# LTC2485Shield.net
KiCad netlist of a schematic drawn in EAGLE
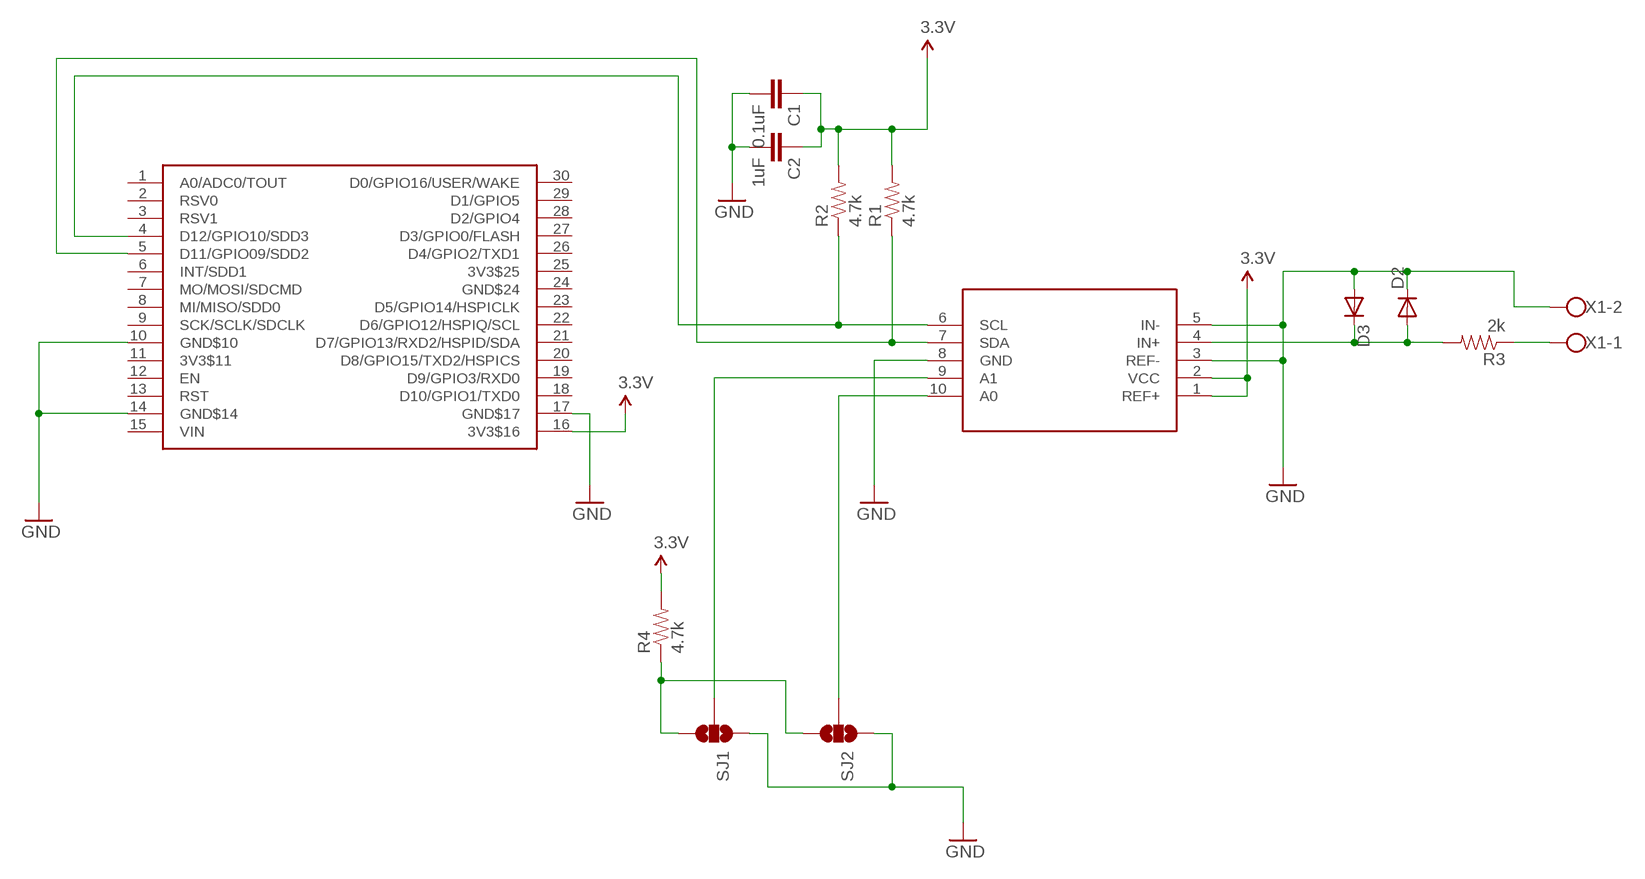
[diagram p0: schematic, sheet 1]

(export (version "E")
  (design (tool "Eeschema 10.0.6"))
  (components
    (comp (ref "C1")
      (value "0.1uF")
      (footprint "eagle-import:0402-CAP")
      (libsource (lib "eagle-import") (part "CAP0402-CAP"))
    )
    (comp (ref "C2")
      (value "1uF")
      (footprint "eagle-import:0402-CAP")
      (libsource (lib "eagle-import") (part "CAP0402-CAP"))
    )
    (comp (ref "D2")
      (value "DIODESOD")
      (footprint "eagle-import:SOD-323")
      (libsource (lib "eagle-import") (part "DIODESOD"))
    )
    (comp (ref "D3")
      (value "DIODESOD")
      (footprint "eagle-import:SOD-323")
      (libsource (lib "eagle-import") (part "DIODESOD"))
    )
    (comp (ref "R1")
      (value "4.7k")
      (footprint "eagle-import:0402-RES")
      (libsource (lib "eagle-import") (part "RESISTOR0402-RES"))
    )
    (comp (ref "R2")
      (value "4.7k")
      (footprint "eagle-import:0402-RES")
      (libsource (lib "eagle-import") (part "RESISTOR0402-RES"))
    )
    (comp (ref "R3")
      (value "2k")
      (footprint "eagle-import:0402-RES")
      (libsource (lib "eagle-import") (part "RESISTOR0402-RES"))
    )
    (comp (ref "R4")
      (value "4.7k")
      (footprint "eagle-import:0402-RES")
      (libsource (lib "eagle-import") (part "RESISTOR0402-RES"))
    )
    (comp (ref "SJ1")
      (value "SOLDERJUMPER_2WAYT")
      (footprint "eagle-import:SJ_2")
      (libsource (lib "eagle-import") (part "SOLDERJUMPER_2WAYT"))
    )
    (comp (ref "SJ2")
      (value "SOLDERJUMPER_2WAYT")
      (footprint "eagle-import:SJ_2")
      (libsource (lib "eagle-import") (part "SOLDERJUMPER_2WAYT"))
    )
    (comp (ref "U$1")
      (value "NERDSHIELD")
      (footprint "eagle-import:NERDUINO_STACK")
      (libsource (lib "eagle-import") (part "NERDSHIELD"))
    )
    (comp (ref "U$2")
      (value "LTC2485")
      (footprint "eagle-import:DFN10-3X3")
      (libsource (lib "eagle-import") (part "LTC2485"))
    )
    (comp (ref "X1")
      (value "W237-102")
      (footprint "eagle-import:W237-102")
      (fields (field (name "MPN") "237-102"))
      (libsource (lib "eagle-import") (part "W237-102"))
    )
  )
  (nets
    (net (code "1") (name "3.3V") (class "Default")
      (node (ref "C1") (pin "1") (pinfunction "1_1") (pintype "passive"))
      (node (ref "C2") (pin "1") (pinfunction "1_1") (pintype "passive"))
      (node (ref "R1") (pin "2") (pinfunction "2_2") (pintype "passive"))
      (node (ref "R2") (pin "2") (pinfunction "2_2") (pintype "passive"))
      (node (ref "R4") (pin "2") (pinfunction "2_2") (pintype "passive"))
      (node (ref "U$1") (pin "16") (pinfunction "3V3$16_16") (pintype "bidirectional"))
      (node (ref "U$2") (pin "1") (pinfunction "REF+_1") (pintype "bidirectional"))
      (node (ref "U$2") (pin "2") (pinfunction "VCC_2") (pintype "bidirectional"))
    )
    (net (code "2") (name "GND") (class "Default")
      (node (ref "C1") (pin "2") (pinfunction "2_2") (pintype "passive"))
      (node (ref "C2") (pin "2") (pinfunction "2_2") (pintype "passive"))
      (node (ref "D2") (pin "1") (pinfunction "C_1") (pintype "passive"))
      (node (ref "D3") (pin "2") (pinfunction "A_2") (pintype "passive"))
      (node (ref "SJ1") (pin "1") (pinfunction "1_1") (pintype "passive"))
      (node (ref "SJ2") (pin "1") (pinfunction "1_1") (pintype "passive"))
      (node (ref "U$1") (pin "10") (pinfunction "GND$10_10") (pintype "bidirectional"))
      (node (ref "U$1") (pin "14") (pinfunction "GND$14_14") (pintype "bidirectional"))
      (node (ref "U$1") (pin "17") (pinfunction "GND$17_17") (pintype "bidirectional"))
      (node (ref "U$2") (pin "3") (pinfunction "REF-_3") (pintype "bidirectional"))
      (node (ref "U$2") (pin "5") (pinfunction "IN-_5") (pintype "bidirectional"))
      (node (ref "U$2") (pin "8") (pinfunction "GND_8") (pintype "bidirectional"))
      (node (ref "X1") (pin "2") (pinfunction "KL_2") (pintype "passive"))
    )
    (net (code "3") (name "Net-(D2-A)") (class "Default")
      (node (ref "D2") (pin "2") (pinfunction "A_2") (pintype "passive"))
      (node (ref "D3") (pin "1") (pinfunction "C_1") (pintype "passive"))
      (node (ref "R3") (pin "2") (pinfunction "2_2") (pintype "passive"))
      (node (ref "U$2") (pin "4") (pinfunction "IN+_4") (pintype "bidirectional"))
    )
    (net (code "4") (name "Net-(R4-Pad1)") (class "Default")
      (node (ref "R4") (pin "1") (pinfunction "1_1") (pintype "passive"))
      (node (ref "SJ1") (pin "3") (pinfunction "3_3") (pintype "passive"))
      (node (ref "SJ2") (pin "3") (pinfunction "3_3") (pintype "passive"))
    )
    (net (code "5") (name "Net-(U$1-D11{slash}GPIO09{slash}SDD2)") (class "Default")
      (node (ref "R1") (pin "1") (pinfunction "1_1") (pintype "passive"))
      (node (ref "U$1") (pin "5") (pinfunction "D11/GPIO09/SDD2_5") (pintype "bidirectional"))
      (node (ref "U$2") (pin "7") (pinfunction "SDA_7") (pintype "bidirectional"))
    )
    (net (code "6") (name "Net-(U$1-D12{slash}GPIO10{slash}SDD3)") (class "Default")
      (node (ref "R2") (pin "1") (pinfunction "1_1") (pintype "passive"))
      (node (ref "U$1") (pin "4") (pinfunction "D12/GPIO10/SDD3_4") (pintype "bidirectional"))
      (node (ref "U$2") (pin "6") (pinfunction "SCL_6") (pintype "bidirectional"))
    )
    (net (code "7") (name "Net-(U$2-A0)") (class "Default")
      (node (ref "SJ2") (pin "2") (pinfunction "2_2") (pintype "passive"))
      (node (ref "U$2") (pin "10") (pinfunction "A0_10") (pintype "bidirectional"))
    )
    (net (code "8") (name "Net-(U$2-A1)") (class "Default")
      (node (ref "SJ1") (pin "2") (pinfunction "2_2") (pintype "passive"))
      (node (ref "U$2") (pin "9") (pinfunction "A1_9") (pintype "bidirectional"))
    )
    (net (code "9") (name "Net-(X1A-KL)") (class "Default")
      (node (ref "R3") (pin "1") (pinfunction "1_1") (pintype "passive"))
      (node (ref "X1") (pin "1") (pinfunction "KL_1") (pintype "passive"))
    )
    (net (code "10") (name "unconnected-(U$1-3V3$11-Pad11)") (class "Default")
      (node (ref "U$1") (pin "11") (pinfunction "3V3$11_11") (pintype "bidirectional"))
    )
    (net (code "11") (name "unconnected-(U$1-3V3$25-Pad25)") (class "Default")
      (node (ref "U$1") (pin "25") (pinfunction "3V3$25_25") (pintype "bidirectional"))
    )
    (net (code "12") (name "unconnected-(U$1-A0{slash}ADC0{slash}TOUT-Pad1)") (class "Default")
      (node (ref "U$1") (pin "1") (pinfunction "A0/ADC0/TOUT_1") (pintype "bidirectional"))
    )
    (net (code "13") (name "unconnected-(U$1-D0{slash}GPIO16{slash}USER{slash}WAKE-Pad30)") (class "Default")
      (node (ref "U$1") (pin "30") (pinfunction "D0/GPIO16/USER/WAKE_30") (pintype "bidirectional"))
    )
    (net (code "14") (name "unconnected-(U$1-D1{slash}GPIO5-Pad29)") (class "Default")
      (node (ref "U$1") (pin "29") (pinfunction "D1/GPIO5_29") (pintype "bidirectional"))
    )
    (net (code "15") (name "unconnected-(U$1-D2{slash}GPIO4-Pad28)") (class "Default")
      (node (ref "U$1") (pin "28") (pinfunction "D2/GPIO4_28") (pintype "bidirectional"))
    )
    (net (code "16") (name "unconnected-(U$1-D3{slash}GPIO0{slash}FLASH-Pad27)") (class "Default")
      (node (ref "U$1") (pin "27") (pinfunction "D3/GPIO0/FLASH_27") (pintype "bidirectional"))
    )
    (net (code "17") (name "unconnected-(U$1-D4{slash}GPIO2{slash}TXD1-Pad26)") (class "Default")
      (node (ref "U$1") (pin "26") (pinfunction "D4/GPIO2/TXD1_26") (pintype "bidirectional"))
    )
    (net (code "18") (name "unconnected-(U$1-D5{slash}GPIO14{slash}HSPICLK-Pad23)") (class "Default")
      (node (ref "U$1") (pin "23") (pinfunction "D5/GPIO14/HSPICLK_23") (pintype "bidirectional"))
    )
    (net (code "19") (name "unconnected-(U$1-D6{slash}GPIO12{slash}HSPIQ{slash}SCL-Pad22)") (class "Default")
      (node (ref "U$1") (pin "22") (pinfunction "D6/GPIO12/HSPIQ/SCL_22") (pintype "bidirectional"))
    )
    (net (code "20") (name "unconnected-(U$1-D7{slash}GPIO13{slash}RXD2{slash}HSPID{slash}SDA-Pad21)") (class "Default")
      (node (ref "U$1") (pin "21") (pinfunction "D7/GPIO13/RXD2/HSPID/SDA_21") (pintype "bidirectional"))
    )
    (net (code "21") (name "unconnected-(U$1-D8{slash}GPIO15{slash}TXD2{slash}HSPICS-Pad20)") (class "Default")
      (node (ref "U$1") (pin "20") (pinfunction "D8/GPIO15/TXD2/HSPICS_20") (pintype "bidirectional"))
    )
    (net (code "22") (name "unconnected-(U$1-D9{slash}GPIO3{slash}RXD0-Pad19)") (class "Default")
      (node (ref "U$1") (pin "19") (pinfunction "D9/GPIO3/RXD0_19") (pintype "bidirectional"))
    )
    (net (code "23") (name "unconnected-(U$1-D10{slash}GPIO1{slash}TXD0-Pad18)") (class "Default")
      (node (ref "U$1") (pin "18") (pinfunction "D10/GPIO1/TXD0_18") (pintype "bidirectional"))
    )
    (net (code "24") (name "unconnected-(U$1-EN-Pad12)") (class "Default")
      (node (ref "U$1") (pin "12") (pinfunction "EN_12") (pintype "bidirectional"))
    )
    (net (code "25") (name "unconnected-(U$1-GND$24-Pad24)") (class "Default")
      (node (ref "U$1") (pin "24") (pinfunction "GND$24_24") (pintype "bidirectional"))
    )
    (net (code "26") (name "unconnected-(U$1-INT{slash}SDD1-Pad6)") (class "Default")
      (node (ref "U$1") (pin "6") (pinfunction "INT/SDD1_6") (pintype "bidirectional"))
    )
    (net (code "27") (name "unconnected-(U$1-MI{slash}MISO{slash}SDD0-Pad8)") (class "Default")
      (node (ref "U$1") (pin "8") (pinfunction "MI/MISO/SDD0_8") (pintype "bidirectional"))
    )
    (net (code "28") (name "unconnected-(U$1-MO{slash}MOSI{slash}SDCMD-Pad7)") (class "Default")
      (node (ref "U$1") (pin "7") (pinfunction "MO/MOSI/SDCMD_7") (pintype "bidirectional"))
    )
    (net (code "29") (name "unconnected-(U$1-RST-Pad13)") (class "Default")
      (node (ref "U$1") (pin "13") (pinfunction "RST_13") (pintype "bidirectional"))
    )
    (net (code "30") (name "unconnected-(U$1-RSV0-Pad2)") (class "Default")
      (node (ref "U$1") (pin "2") (pinfunction "RSV0_2") (pintype "bidirectional"))
    )
    (net (code "31") (name "unconnected-(U$1-RSV1-Pad3)") (class "Default")
      (node (ref "U$1") (pin "3") (pinfunction "RSV1_3") (pintype "bidirectional"))
    )
    (net (code "32") (name "unconnected-(U$1-SCK{slash}SCLK{slash}SDCLK-Pad9)") (class "Default")
      (node (ref "U$1") (pin "9") (pinfunction "SCK/SCLK/SDCLK_9") (pintype "bidirectional"))
    )
    (net (code "33") (name "unconnected-(U$1-VIN-Pad15)") (class "Default")
      (node (ref "U$1") (pin "15") (pinfunction "VIN_15") (pintype "bidirectional"))
    )
  )
)
